# pilot.net
KiCad netlist of a schematic drawn in EAGLE
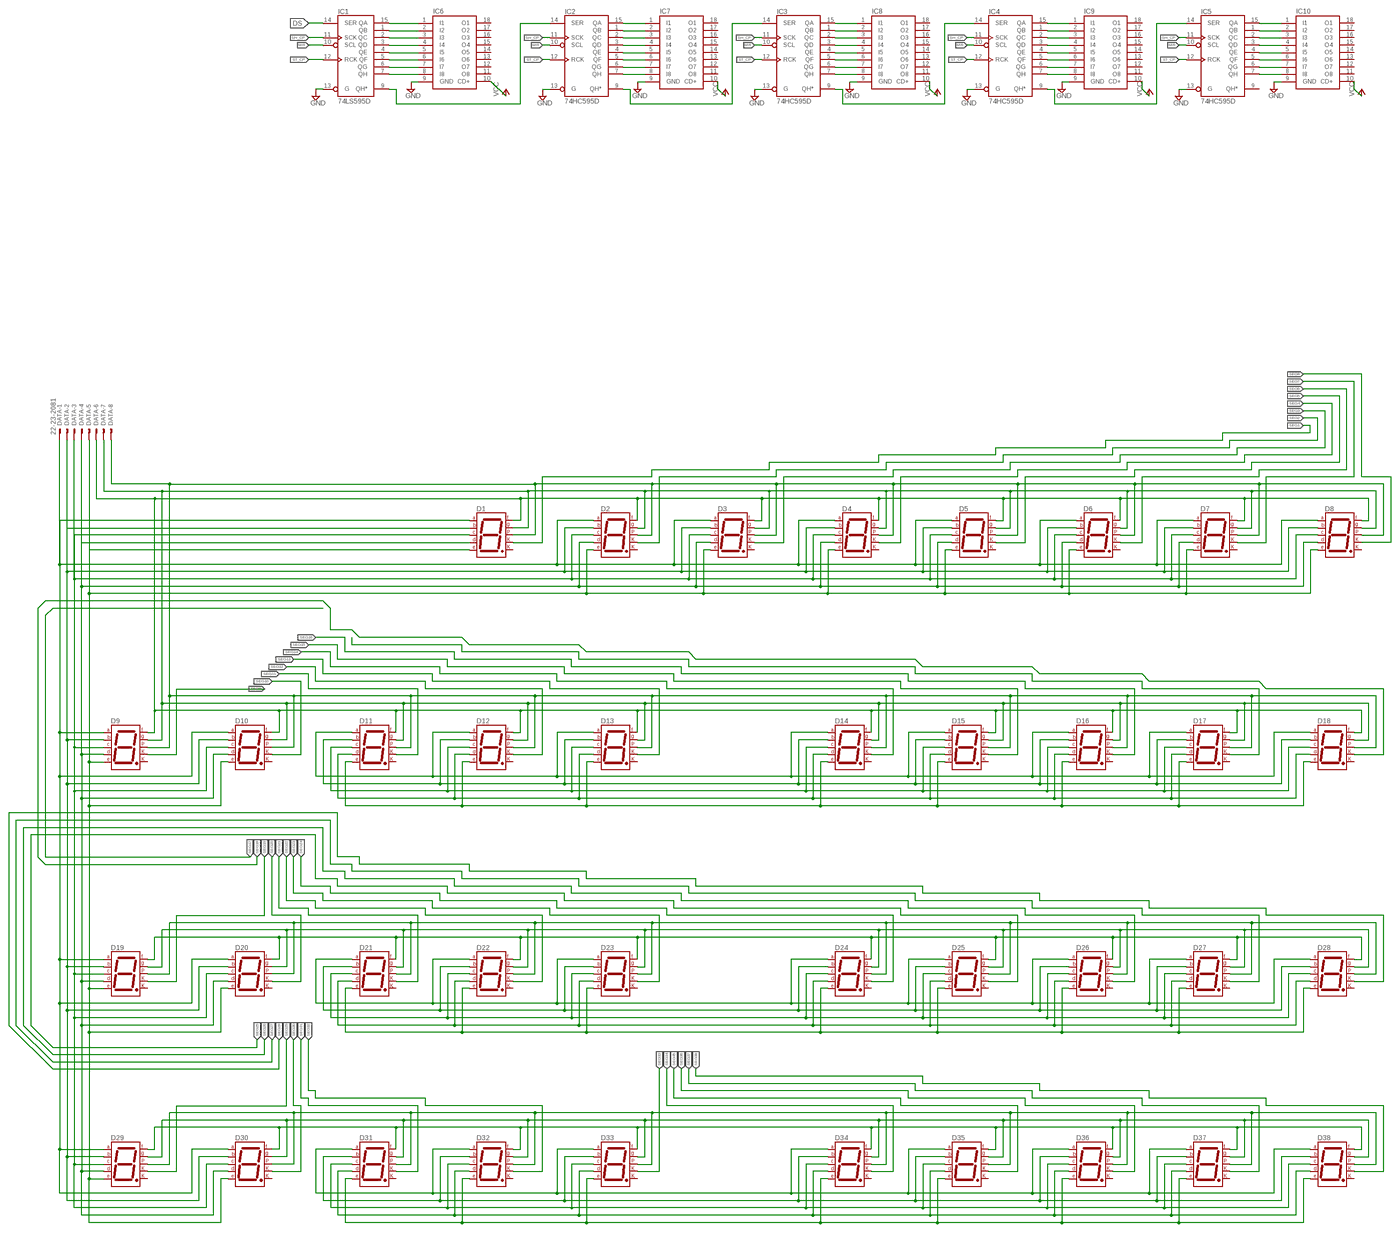
[diagram p0: schematic, sheet 1, overview]
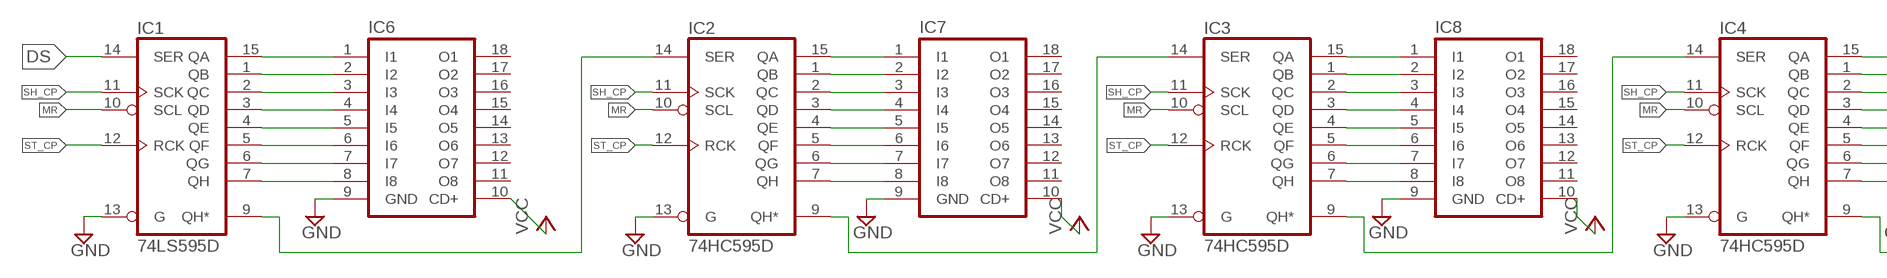
[diagram p1: schematic, sheet 1, part 1 of 4]
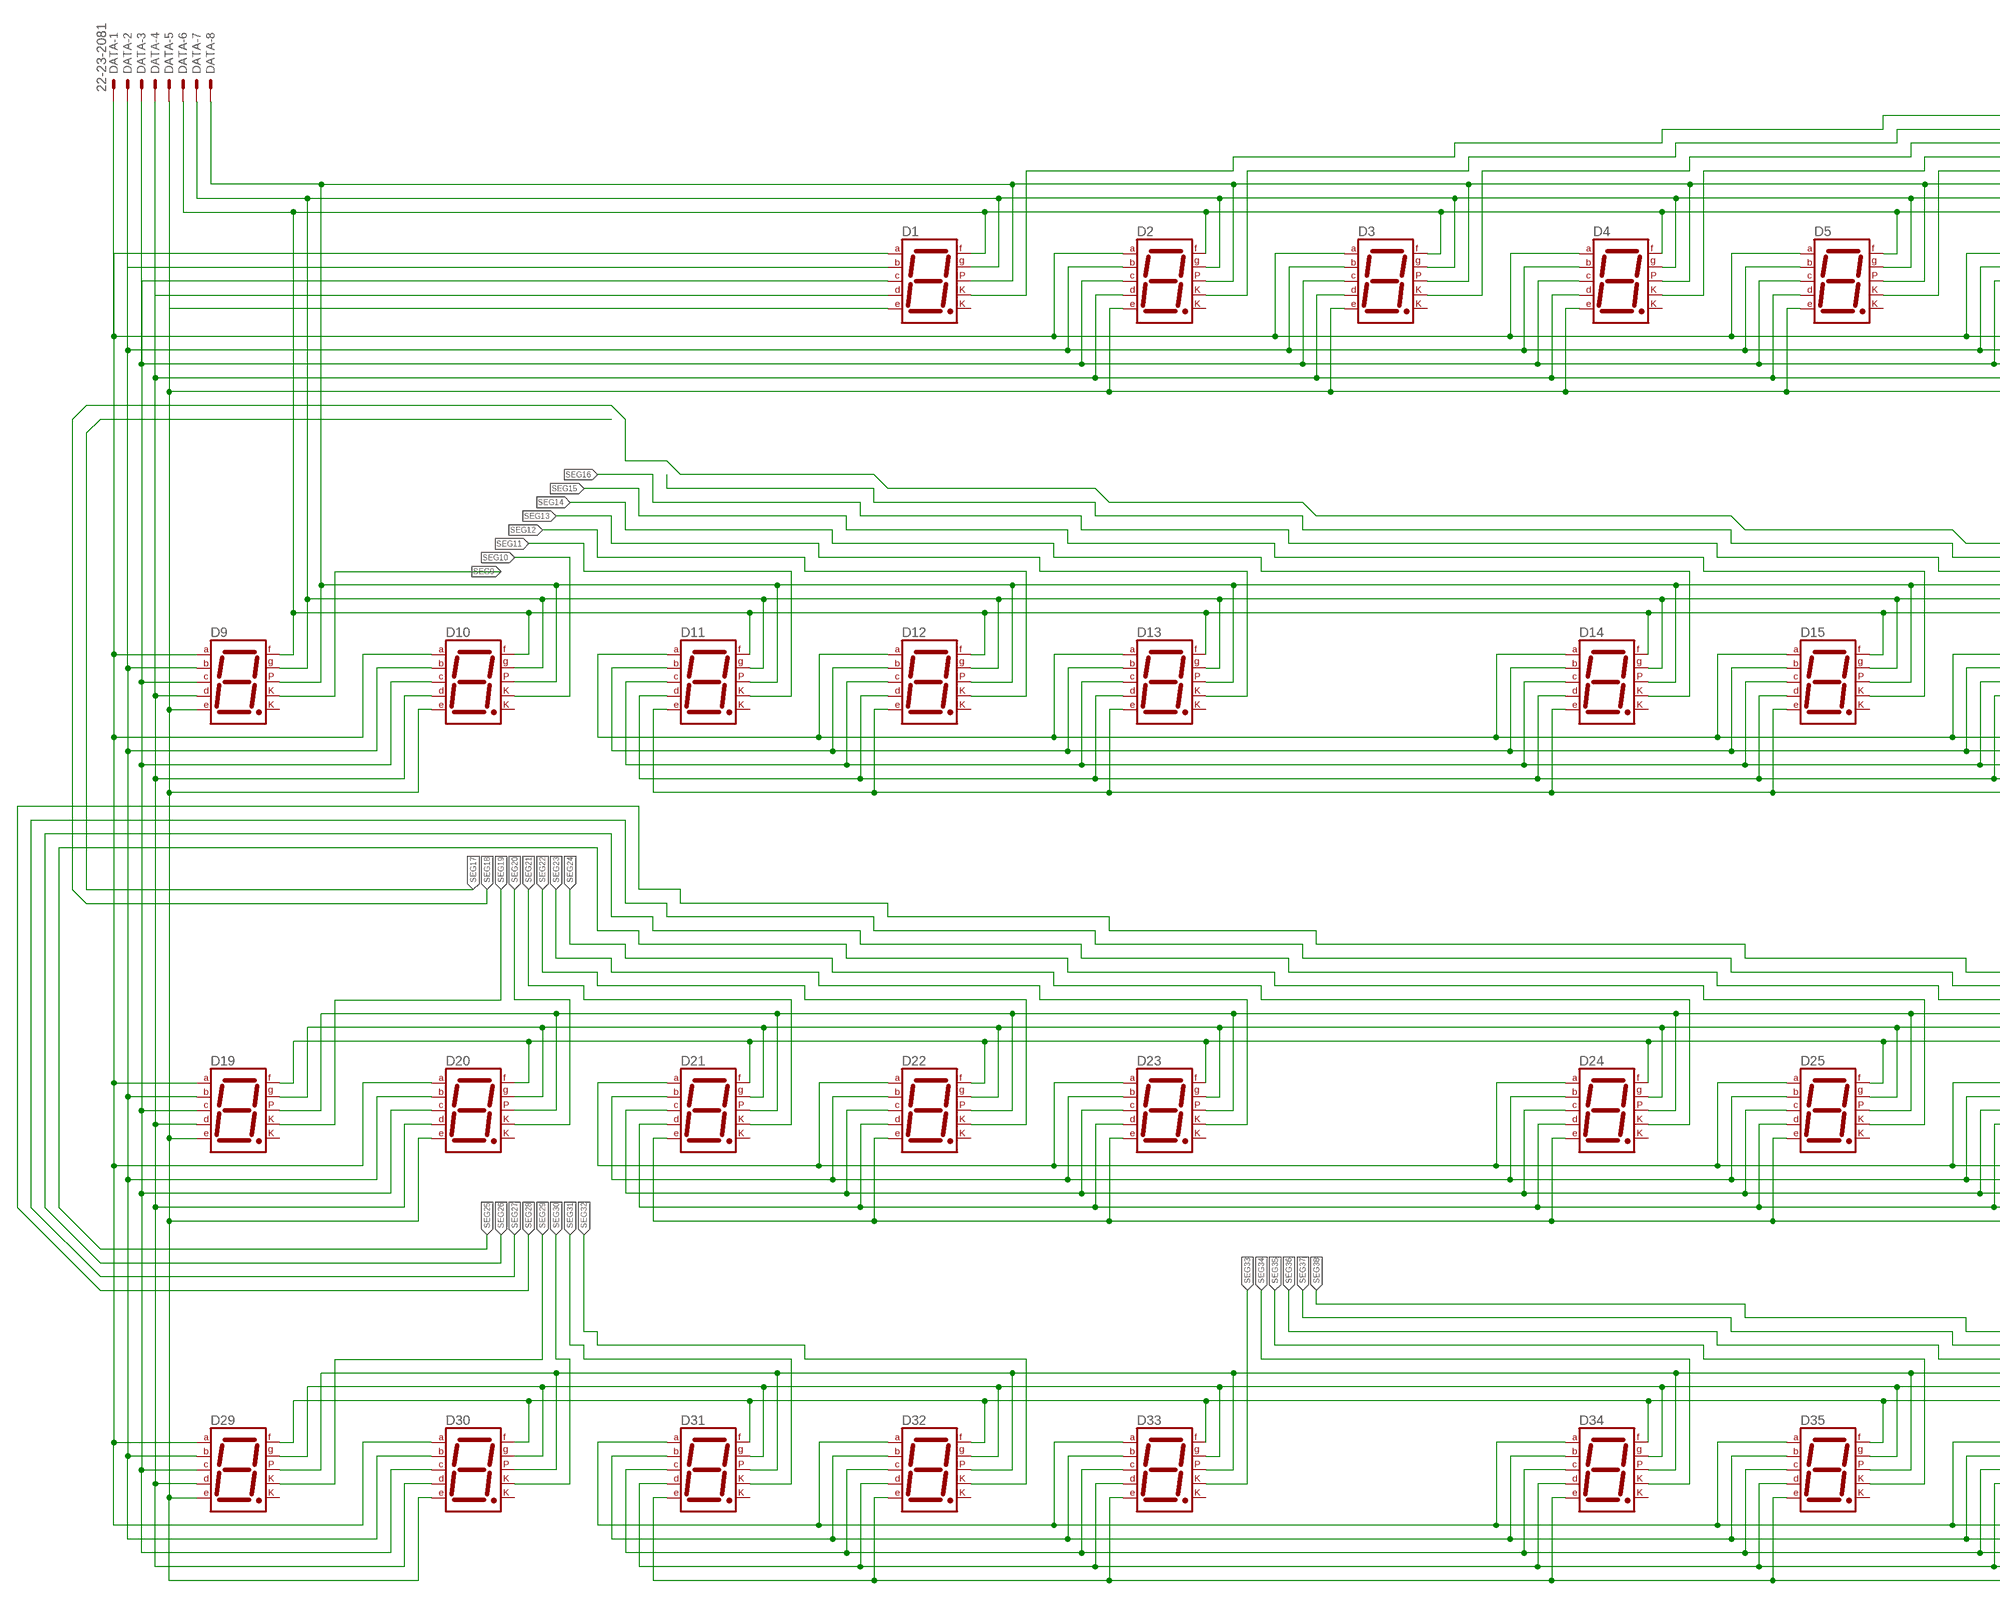
[diagram p2: schematic, sheet 1, part 2 of 4]
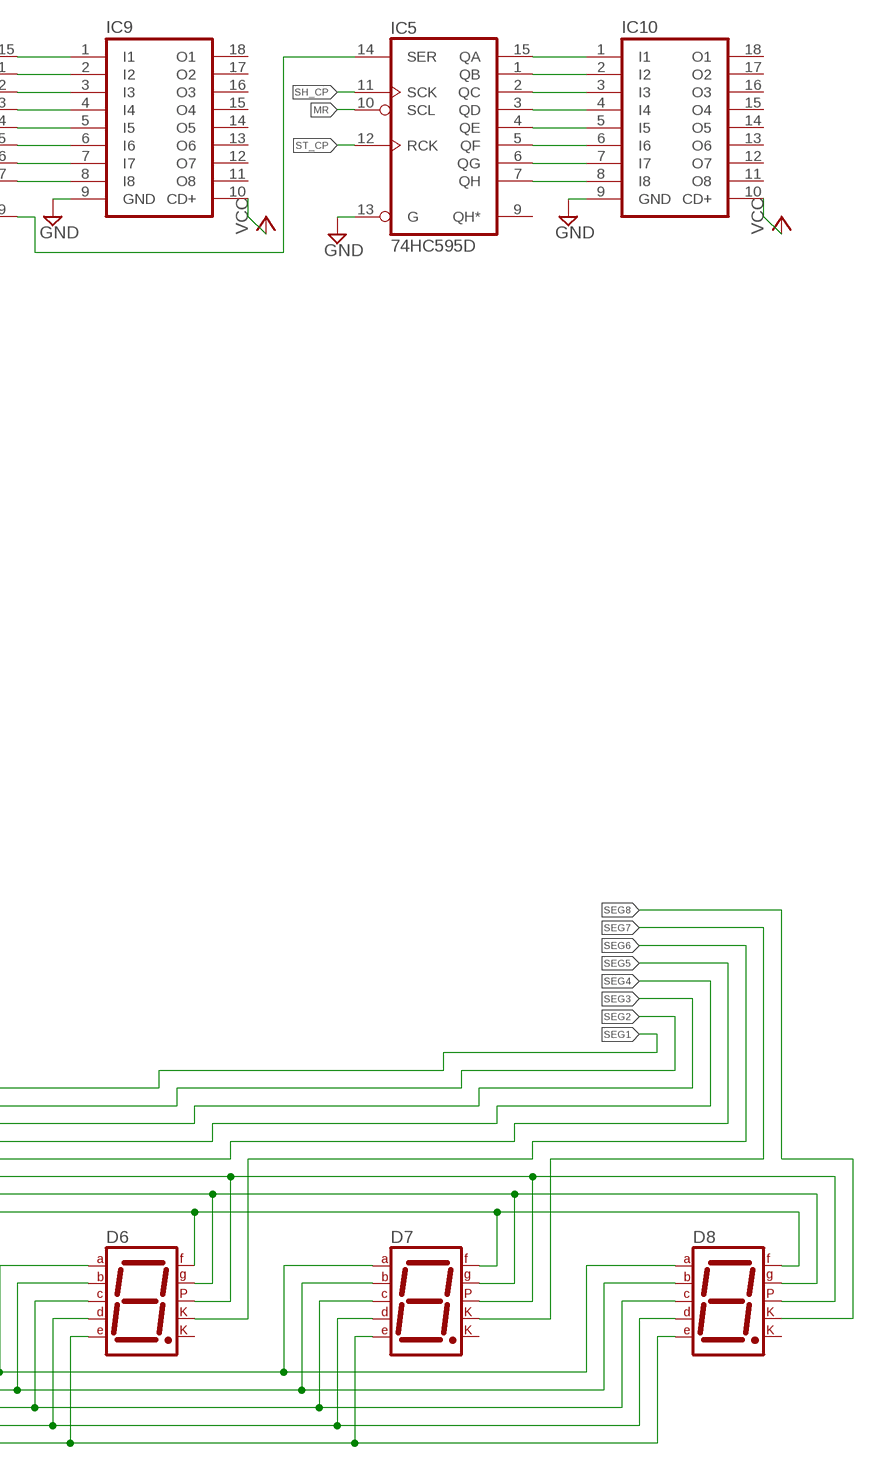
[diagram p3: schematic, sheet 1, part 3 of 4]
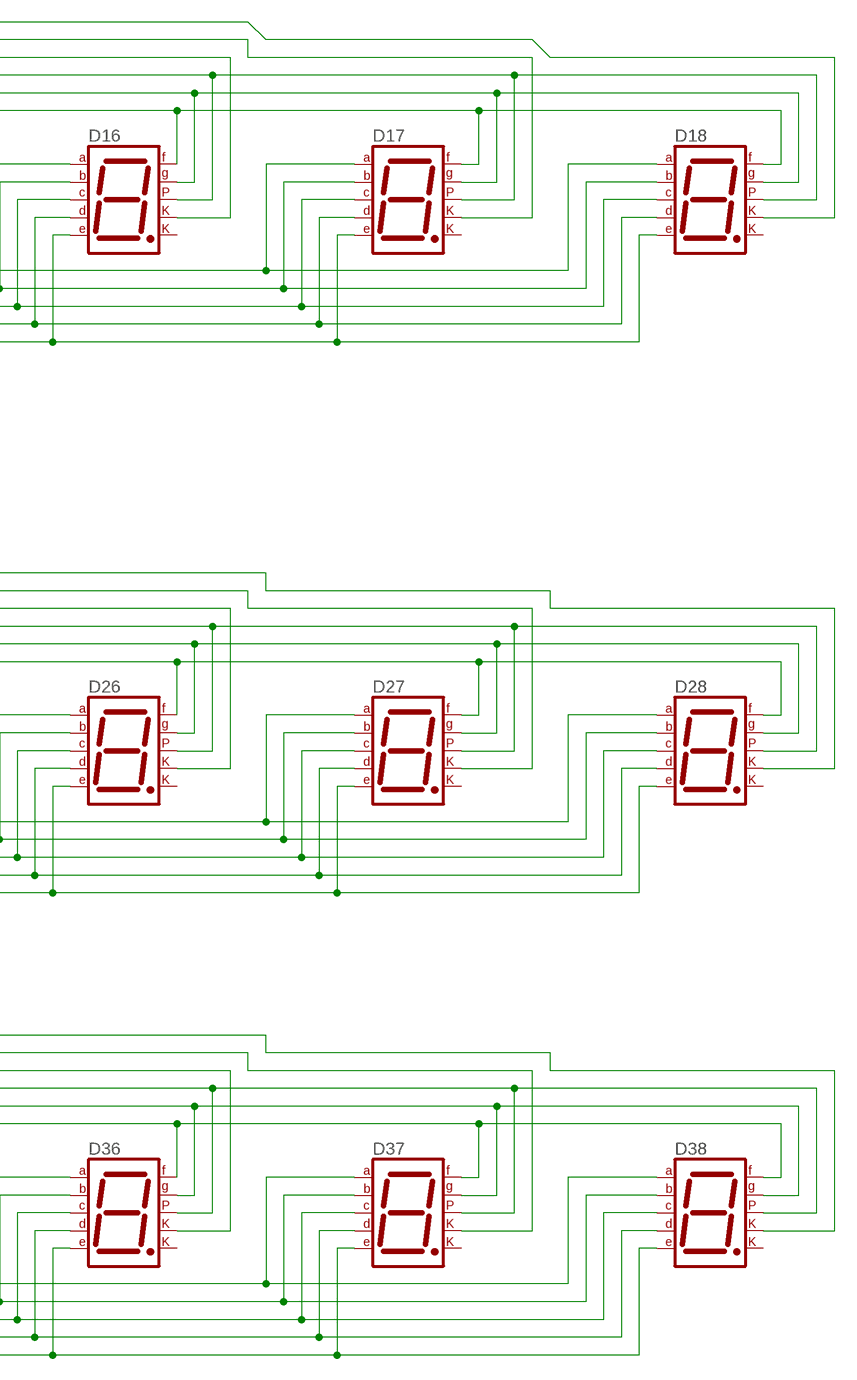
[diagram p4: schematic, sheet 1, part 4 of 4]

(export (version "E")
  (design (tool "Eeschema 10.0.6"))
  (components
    (comp (ref "D1")
      (value "7SEG-CK")
      (footprint "eagle-import:7SEG-13")
      (libsource (lib "eagle-import") (part "7SEG-CK"))
    )
    (comp (ref "D2")
      (value "7SEG-CK")
      (footprint "eagle-import:7SEG-13")
      (libsource (lib "eagle-import") (part "7SEG-CK"))
    )
    (comp (ref "D3")
      (value "7SEG-CK")
      (footprint "eagle-import:7SEG-13")
      (libsource (lib "eagle-import") (part "7SEG-CK"))
    )
    (comp (ref "D4")
      (value "7SEG-CK")
      (footprint "eagle-import:7SEG-13")
      (libsource (lib "eagle-import") (part "7SEG-CK"))
    )
    (comp (ref "D5")
      (value "7SEG-CK")
      (footprint "eagle-import:7SEG-13")
      (libsource (lib "eagle-import") (part "7SEG-CK"))
    )
    (comp (ref "D6")
      (value "7SEG-CK")
      (footprint "eagle-import:7SEG-13")
      (libsource (lib "eagle-import") (part "7SEG-CK"))
    )
    (comp (ref "D7")
      (value "7SEG-CK")
      (footprint "eagle-import:7SEG-13")
      (libsource (lib "eagle-import") (part "7SEG-CK"))
    )
    (comp (ref "D8")
      (value "7SEG-CK")
      (footprint "eagle-import:7SEG-13")
      (libsource (lib "eagle-import") (part "7SEG-CK"))
    )
    (comp (ref "D9")
      (value "7SEG-CK")
      (footprint "eagle-import:7SEG-13")
      (libsource (lib "eagle-import") (part "7SEG-CK"))
    )
    (comp (ref "D10")
      (value "7SEG-CK")
      (footprint "eagle-import:7SEG-13")
      (libsource (lib "eagle-import") (part "7SEG-CK"))
    )
    (comp (ref "D11")
      (value "7SEG-CK")
      (footprint "eagle-import:7SEG-13")
      (libsource (lib "eagle-import") (part "7SEG-CK"))
    )
    (comp (ref "D12")
      (value "7SEG-CK")
      (footprint "eagle-import:7SEG-13")
      (libsource (lib "eagle-import") (part "7SEG-CK"))
    )
    (comp (ref "D13")
      (value "7SEG-CK")
      (footprint "eagle-import:7SEG-13")
      (libsource (lib "eagle-import") (part "7SEG-CK"))
    )
    (comp (ref "D14")
      (value "7SEG-CK")
      (footprint "eagle-import:7SEG-13")
      (libsource (lib "eagle-import") (part "7SEG-CK"))
    )
    (comp (ref "D15")
      (value "7SEG-CK")
      (footprint "eagle-import:7SEG-13")
      (libsource (lib "eagle-import") (part "7SEG-CK"))
    )
    (comp (ref "D16")
      (value "7SEG-CK")
      (footprint "eagle-import:7SEG-13")
      (libsource (lib "eagle-import") (part "7SEG-CK"))
    )
    (comp (ref "D17")
      (value "7SEG-CK")
      (footprint "eagle-import:7SEG-13")
      (libsource (lib "eagle-import") (part "7SEG-CK"))
    )
    (comp (ref "D18")
      (value "7SEG-CK")
      (footprint "eagle-import:7SEG-13")
      (libsource (lib "eagle-import") (part "7SEG-CK"))
    )
    (comp (ref "D19")
      (value "7SEG-CK")
      (footprint "eagle-import:7SEG-13")
      (libsource (lib "eagle-import") (part "7SEG-CK"))
    )
    (comp (ref "D20")
      (value "7SEG-CK")
      (footprint "eagle-import:7SEG-13")
      (libsource (lib "eagle-import") (part "7SEG-CK"))
    )
    (comp (ref "D21")
      (value "7SEG-CK")
      (footprint "eagle-import:7SEG-13")
      (libsource (lib "eagle-import") (part "7SEG-CK"))
    )
    (comp (ref "D22")
      (value "7SEG-CK")
      (footprint "eagle-import:7SEG-13")
      (libsource (lib "eagle-import") (part "7SEG-CK"))
    )
    (comp (ref "D23")
      (value "7SEG-CK")
      (footprint "eagle-import:7SEG-13")
      (libsource (lib "eagle-import") (part "7SEG-CK"))
    )
    (comp (ref "D24")
      (value "7SEG-CK")
      (footprint "eagle-import:7SEG-13")
      (libsource (lib "eagle-import") (part "7SEG-CK"))
    )
    (comp (ref "D25")
      (value "7SEG-CK")
      (footprint "eagle-import:7SEG-13")
      (libsource (lib "eagle-import") (part "7SEG-CK"))
    )
    (comp (ref "D26")
      (value "7SEG-CK")
      (footprint "eagle-import:7SEG-13")
      (libsource (lib "eagle-import") (part "7SEG-CK"))
    )
    (comp (ref "D27")
      (value "7SEG-CK")
      (footprint "eagle-import:7SEG-13")
      (libsource (lib "eagle-import") (part "7SEG-CK"))
    )
    (comp (ref "D28")
      (value "7SEG-CK")
      (footprint "eagle-import:7SEG-13")
      (libsource (lib "eagle-import") (part "7SEG-CK"))
    )
    (comp (ref "D29")
      (value "7SEG-CK")
      (footprint "eagle-import:7SEG-13")
      (libsource (lib "eagle-import") (part "7SEG-CK"))
    )
    (comp (ref "D30")
      (value "7SEG-CK")
      (footprint "eagle-import:7SEG-13")
      (libsource (lib "eagle-import") (part "7SEG-CK"))
    )
    (comp (ref "D31")
      (value "7SEG-CK")
      (footprint "eagle-import:7SEG-13")
      (libsource (lib "eagle-import") (part "7SEG-CK"))
    )
    (comp (ref "D32")
      (value "7SEG-CK")
      (footprint "eagle-import:7SEG-13")
      (libsource (lib "eagle-import") (part "7SEG-CK"))
    )
    (comp (ref "D33")
      (value "7SEG-CK")
      (footprint "eagle-import:7SEG-13")
      (libsource (lib "eagle-import") (part "7SEG-CK"))
    )
    (comp (ref "D34")
      (value "7SEG-CK")
      (footprint "eagle-import:7SEG-13")
      (libsource (lib "eagle-import") (part "7SEG-CK"))
    )
    (comp (ref "D35")
      (value "7SEG-CK")
      (footprint "eagle-import:7SEG-13")
      (libsource (lib "eagle-import") (part "7SEG-CK"))
    )
    (comp (ref "D36")
      (value "7SEG-CK")
      (footprint "eagle-import:7SEG-13")
      (libsource (lib "eagle-import") (part "7SEG-CK"))
    )
    (comp (ref "D37")
      (value "7SEG-CK")
      (footprint "eagle-import:7SEG-13")
      (libsource (lib "eagle-import") (part "7SEG-CK"))
    )
    (comp (ref "D38")
      (value "7SEG-CK")
      (footprint "eagle-import:7SEG-13")
      (libsource (lib "eagle-import") (part "7SEG-CK"))
    )
    (comp (ref "DATA")
      (value "22-23-2081")
      (footprint "eagle-import:22-23-2081")
      (fields (field (name "MF") "MOLEX"))
      (libsource (lib "eagle-import") (part "22-23-2081"))
    )
    (comp (ref "IC1")
      (value "74LS595D")
      (footprint "eagle-import:SO16")
      (libsource (lib "eagle-import") (part "74595DLS"))
    )
    (comp (ref "IC2")
      (value "74HC595D")
      (footprint "eagle-import:SO16")
      (libsource (lib "eagle-import") (part "74595DHC"))
    )
    (comp (ref "IC3")
      (value "74HC595D")
      (footprint "eagle-import:SO16")
      (libsource (lib "eagle-import") (part "74595DHC"))
    )
    (comp (ref "IC4")
      (value "74HC595D")
      (footprint "eagle-import:SO16")
      (libsource (lib "eagle-import") (part "74595DHC"))
    )
    (comp (ref "IC5")
      (value "74HC595D")
      (footprint "eagle-import:SO16")
      (libsource (lib "eagle-import") (part "74595DHC"))
    )
    (comp (ref "IC6")
      (value "ULN2803A")
      (footprint "eagle-import:DIL18")
      (libsource (lib "eagle-import") (part "ULN2803A"))
    )
    (comp (ref "IC7")
      (value "ULN2803A")
      (footprint "eagle-import:DIL18")
      (libsource (lib "eagle-import") (part "ULN2803A"))
    )
    (comp (ref "IC8")
      (value "ULN2803A")
      (footprint "eagle-import:DIL18")
      (libsource (lib "eagle-import") (part "ULN2803A"))
    )
    (comp (ref "IC9")
      (value "ULN2803A")
      (footprint "eagle-import:DIL18")
      (libsource (lib "eagle-import") (part "ULN2803A"))
    )
    (comp (ref "IC10")
      (value "ULN2803A")
      (footprint "eagle-import:DIL18")
      (libsource (lib "eagle-import") (part "ULN2803A"))
    )
  )
  (nets
    (net (code "1") (name "DS") (class "Default")
      (node (ref "IC1") (pin "14") (pinfunction "SER_14") (pintype "input"))
    )
    (net (code "2") (name "GND") (class "Default")
      (node (ref "IC1") (pin "13") (pinfunction "G_13") (pintype "input"))
      (node (ref "IC10") (pin "9") (pinfunction "GND_9") (pintype "power_in"))
      (node (ref "IC2") (pin "13") (pinfunction "G_13") (pintype "input"))
      (node (ref "IC3") (pin "13") (pinfunction "G_13") (pintype "input"))
      (node (ref "IC4") (pin "13") (pinfunction "G_13") (pintype "input"))
      (node (ref "IC5") (pin "13") (pinfunction "G_13") (pintype "input"))
      (node (ref "IC6") (pin "9") (pinfunction "GND_9") (pintype "power_in"))
      (node (ref "IC7") (pin "9") (pinfunction "GND_9") (pintype "power_in"))
      (node (ref "IC8") (pin "9") (pinfunction "GND_9") (pintype "power_in"))
      (node (ref "IC9") (pin "9") (pinfunction "GND_9") (pintype "power_in"))
    )
    (net (code "3") (name "MR") (class "Default")
      (node (ref "IC1") (pin "10") (pinfunction "SCL_10") (pintype "input"))
      (node (ref "IC2") (pin "10") (pinfunction "SCL_10") (pintype "input"))
      (node (ref "IC3") (pin "10") (pinfunction "SCL_10") (pintype "input"))
      (node (ref "IC4") (pin "10") (pinfunction "SCL_10") (pintype "input"))
      (node (ref "IC5") (pin "10") (pinfunction "SCL_10") (pintype "input"))
    )
    (net (code "4") (name "Net-(D1-A)") (class "Default")
      (node (ref "D1") (pin "7") (pinfunction "A_7") (pintype "passive"))
      (node (ref "D10") (pin "7") (pinfunction "A_7") (pintype "passive"))
      (node (ref "D19") (pin "7") (pinfunction "A_7") (pintype "passive"))
      (node (ref "D2") (pin "7") (pinfunction "A_7") (pintype "passive"))
      (node (ref "D20") (pin "7") (pinfunction "A_7") (pintype "passive"))
      (node (ref "D29") (pin "7") (pinfunction "A_7") (pintype "passive"))
      (node (ref "D3") (pin "7") (pinfunction "A_7") (pintype "passive"))
      (node (ref "D30") (pin "7") (pinfunction "A_7") (pintype "passive"))
      (node (ref "D4") (pin "7") (pinfunction "A_7") (pintype "passive"))
      (node (ref "D5") (pin "7") (pinfunction "A_7") (pintype "passive"))
      (node (ref "D6") (pin "7") (pinfunction "A_7") (pintype "passive"))
      (node (ref "D7") (pin "7") (pinfunction "A_7") (pintype "passive"))
      (node (ref "D8") (pin "7") (pinfunction "A_7") (pintype "passive"))
      (node (ref "D9") (pin "7") (pinfunction "A_7") (pintype "passive"))
      (node (ref "DATA") (pin "1") (pinfunction "S_1") (pintype "passive"))
    )
    (net (code "5") (name "Net-(D1-B)") (class "Default")
      (node (ref "D1") (pin "6") (pinfunction "B_6") (pintype "passive"))
      (node (ref "D10") (pin "6") (pinfunction "B_6") (pintype "passive"))
      (node (ref "D19") (pin "6") (pinfunction "B_6") (pintype "passive"))
      (node (ref "D2") (pin "6") (pinfunction "B_6") (pintype "passive"))
      (node (ref "D20") (pin "6") (pinfunction "B_6") (pintype "passive"))
      (node (ref "D29") (pin "6") (pinfunction "B_6") (pintype "passive"))
      (node (ref "D3") (pin "6") (pinfunction "B_6") (pintype "passive"))
      (node (ref "D30") (pin "6") (pinfunction "B_6") (pintype "passive"))
      (node (ref "D4") (pin "6") (pinfunction "B_6") (pintype "passive"))
      (node (ref "D5") (pin "6") (pinfunction "B_6") (pintype "passive"))
      (node (ref "D6") (pin "6") (pinfunction "B_6") (pintype "passive"))
      (node (ref "D7") (pin "6") (pinfunction "B_6") (pintype "passive"))
      (node (ref "D8") (pin "6") (pinfunction "B_6") (pintype "passive"))
      (node (ref "D9") (pin "6") (pinfunction "B_6") (pintype "passive"))
      (node (ref "DATA") (pin "2") (pinfunction "S_2") (pintype "passive"))
    )
    (net (code "6") (name "Net-(D1-C)") (class "Default")
      (node (ref "D1") (pin "4") (pinfunction "C_4") (pintype "passive"))
      (node (ref "D10") (pin "4") (pinfunction "C_4") (pintype "passive"))
      (node (ref "D19") (pin "4") (pinfunction "C_4") (pintype "passive"))
      (node (ref "D2") (pin "4") (pinfunction "C_4") (pintype "passive"))
      (node (ref "D20") (pin "4") (pinfunction "C_4") (pintype "passive"))
      (node (ref "D29") (pin "4") (pinfunction "C_4") (pintype "passive"))
      (node (ref "D3") (pin "4") (pinfunction "C_4") (pintype "passive"))
      (node (ref "D30") (pin "4") (pinfunction "C_4") (pintype "passive"))
      (node (ref "D4") (pin "4") (pinfunction "C_4") (pintype "passive"))
      (node (ref "D5") (pin "4") (pinfunction "C_4") (pintype "passive"))
      (node (ref "D6") (pin "4") (pinfunction "C_4") (pintype "passive"))
      (node (ref "D7") (pin "4") (pinfunction "C_4") (pintype "passive"))
      (node (ref "D8") (pin "4") (pinfunction "C_4") (pintype "passive"))
      (node (ref "D9") (pin "4") (pinfunction "C_4") (pintype "passive"))
      (node (ref "DATA") (pin "3") (pinfunction "S_3") (pintype "passive"))
    )
    (net (code "7") (name "Net-(D1-D)") (class "Default")
      (node (ref "D1") (pin "2") (pinfunction "D_2") (pintype "passive"))
      (node (ref "D10") (pin "2") (pinfunction "D_2") (pintype "passive"))
      (node (ref "D19") (pin "2") (pinfunction "D_2") (pintype "passive"))
      (node (ref "D2") (pin "2") (pinfunction "D_2") (pintype "passive"))
      (node (ref "D20") (pin "2") (pinfunction "D_2") (pintype "passive"))
      (node (ref "D29") (pin "2") (pinfunction "D_2") (pintype "passive"))
      (node (ref "D3") (pin "2") (pinfunction "D_2") (pintype "passive"))
      (node (ref "D30") (pin "2") (pinfunction "D_2") (pintype "passive"))
      (node (ref "D4") (pin "2") (pinfunction "D_2") (pintype "passive"))
      (node (ref "D5") (pin "2") (pinfunction "D_2") (pintype "passive"))
      (node (ref "D6") (pin "2") (pinfunction "D_2") (pintype "passive"))
      (node (ref "D7") (pin "2") (pinfunction "D_2") (pintype "passive"))
      (node (ref "D8") (pin "2") (pinfunction "D_2") (pintype "passive"))
      (node (ref "D9") (pin "2") (pinfunction "D_2") (pintype "passive"))
      (node (ref "DATA") (pin "4") (pinfunction "S_4") (pintype "passive"))
    )
    (net (code "8") (name "Net-(D1-DP)") (class "Default")
      (node (ref "D1") (pin "5") (pinfunction "DP_5") (pintype "passive"))
      (node (ref "D10") (pin "5") (pinfunction "DP_5") (pintype "passive"))
      (node (ref "D11") (pin "5") (pinfunction "DP_5") (pintype "passive"))
      (node (ref "D12") (pin "5") (pinfunction "DP_5") (pintype "passive"))
      (node (ref "D13") (pin "5") (pinfunction "DP_5") (pintype "passive"))
      (node (ref "D14") (pin "5") (pinfunction "DP_5") (pintype "passive"))
      (node (ref "D15") (pin "5") (pinfunction "DP_5") (pintype "passive"))
      (node (ref "D16") (pin "5") (pinfunction "DP_5") (pintype "passive"))
      (node (ref "D17") (pin "5") (pinfunction "DP_5") (pintype "passive"))
      (node (ref "D18") (pin "5") (pinfunction "DP_5") (pintype "passive"))
      (node (ref "D2") (pin "5") (pinfunction "DP_5") (pintype "passive"))
      (node (ref "D3") (pin "5") (pinfunction "DP_5") (pintype "passive"))
      (node (ref "D4") (pin "5") (pinfunction "DP_5") (pintype "passive"))
      (node (ref "D5") (pin "5") (pinfunction "DP_5") (pintype "passive"))
      (node (ref "D6") (pin "5") (pinfunction "DP_5") (pintype "passive"))
      (node (ref "D7") (pin "5") (pinfunction "DP_5") (pintype "passive"))
      (node (ref "D8") (pin "5") (pinfunction "DP_5") (pintype "passive"))
      (node (ref "D9") (pin "5") (pinfunction "DP_5") (pintype "passive"))
      (node (ref "DATA") (pin "8") (pinfunction "S_8") (pintype "passive"))
    )
    (net (code "9") (name "Net-(D1-E)") (class "Default")
      (node (ref "D1") (pin "1") (pinfunction "E_1") (pintype "passive"))
      (node (ref "D10") (pin "1") (pinfunction "E_1") (pintype "passive"))
      (node (ref "D19") (pin "1") (pinfunction "E_1") (pintype "passive"))
      (node (ref "D2") (pin "1") (pinfunction "E_1") (pintype "passive"))
      (node (ref "D20") (pin "1") (pinfunction "E_1") (pintype "passive"))
      (node (ref "D29") (pin "1") (pinfunction "E_1") (pintype "passive"))
      (node (ref "D3") (pin "1") (pinfunction "E_1") (pintype "passive"))
      (node (ref "D30") (pin "1") (pinfunction "E_1") (pintype "passive"))
      (node (ref "D4") (pin "1") (pinfunction "E_1") (pintype "passive"))
      (node (ref "D5") (pin "1") (pinfunction "E_1") (pintype "passive"))
      (node (ref "D6") (pin "1") (pinfunction "E_1") (pintype "passive"))
      (node (ref "D7") (pin "1") (pinfunction "E_1") (pintype "passive"))
      (node (ref "D8") (pin "1") (pinfunction "E_1") (pintype "passive"))
      (node (ref "D9") (pin "1") (pinfunction "E_1") (pintype "passive"))
      (node (ref "DATA") (pin "5") (pinfunction "S_5") (pintype "passive"))
    )
    (net (code "10") (name "Net-(D1-F)") (class "Default")
      (node (ref "D1") (pin "9") (pinfunction "F_9") (pintype "passive"))
      (node (ref "D10") (pin "9") (pinfunction "F_9") (pintype "passive"))
      (node (ref "D11") (pin "9") (pinfunction "F_9") (pintype "passive"))
      (node (ref "D12") (pin "9") (pinfunction "F_9") (pintype "passive"))
      (node (ref "D13") (pin "9") (pinfunction "F_9") (pintype "passive"))
      (node (ref "D14") (pin "9") (pinfunction "F_9") (pintype "passive"))
      (node (ref "D15") (pin "9") (pinfunction "F_9") (pintype "passive"))
      (node (ref "D16") (pin "9") (pinfunction "F_9") (pintype "passive"))
      (node (ref "D17") (pin "9") (pinfunction "F_9") (pintype "passive"))
      (node (ref "D18") (pin "9") (pinfunction "F_9") (pintype "passive"))
      (node (ref "D2") (pin "9") (pinfunction "F_9") (pintype "passive"))
      (node (ref "D3") (pin "9") (pinfunction "F_9") (pintype "passive"))
      (node (ref "D4") (pin "9") (pinfunction "F_9") (pintype "passive"))
      (node (ref "D5") (pin "9") (pinfunction "F_9") (pintype "passive"))
      (node (ref "D6") (pin "9") (pinfunction "F_9") (pintype "passive"))
      (node (ref "D7") (pin "9") (pinfunction "F_9") (pintype "passive"))
      (node (ref "D8") (pin "9") (pinfunction "F_9") (pintype "passive"))
      (node (ref "D9") (pin "9") (pinfunction "F_9") (pintype "passive"))
      (node (ref "DATA") (pin "6") (pinfunction "S_6") (pintype "passive"))
    )
    (net (code "11") (name "Net-(D1-G)") (class "Default")
      (node (ref "D1") (pin "10") (pinfunction "G_10") (pintype "passive"))
      (node (ref "D10") (pin "10") (pinfunction "G_10") (pintype "passive"))
      (node (ref "D11") (pin "10") (pinfunction "G_10") (pintype "passive"))
      (node (ref "D12") (pin "10") (pinfunction "G_10") (pintype "passive"))
      (node (ref "D13") (pin "10") (pinfunction "G_10") (pintype "passive"))
      (node (ref "D2") (pin "10") (pinfunction "G_10") (pintype "passive"))
      (node (ref "D3") (pin "10") (pinfunction "G_10") (pintype "passive"))
      (node (ref "D4") (pin "10") (pinfunction "G_10") (pintype "passive"))
      (node (ref "D5") (pin "10") (pinfunction "G_10") (pintype "passive"))
      (node (ref "D6") (pin "10") (pinfunction "G_10") (pintype "passive"))
      (node (ref "D7") (pin "10") (pinfunction "G_10") (pintype "passive"))
      (node (ref "D8") (pin "10") (pinfunction "G_10") (pintype "passive"))
      (node (ref "D9") (pin "10") (pinfunction "G_10") (pintype "passive"))
      (node (ref "DATA") (pin "7") (pinfunction "S_7") (pintype "passive"))
    )
    (net (code "12") (name "Net-(D11-A)") (class "Default")
      (node (ref "D11") (pin "7") (pinfunction "A_7") (pintype "passive"))
      (node (ref "D12") (pin "7") (pinfunction "A_7") (pintype "passive"))
      (node (ref "D13") (pin "7") (pinfunction "A_7") (pintype "passive"))
    )
    (net (code "13") (name "Net-(D11-B)") (class "Default")
      (node (ref "D11") (pin "6") (pinfunction "B_6") (pintype "passive"))
      (node (ref "D12") (pin "6") (pinfunction "B_6") (pintype "passive"))
      (node (ref "D13") (pin "6") (pinfunction "B_6") (pintype "passive"))
    )
    (net (code "14") (name "Net-(D11-C)") (class "Default")
      (node (ref "D11") (pin "4") (pinfunction "C_4") (pintype "passive"))
      (node (ref "D12") (pin "4") (pinfunction "C_4") (pintype "passive"))
      (node (ref "D13") (pin "4") (pinfunction "C_4") (pintype "passive"))
    )
    (net (code "15") (name "Net-(D11-D)") (class "Default")
      (node (ref "D11") (pin "2") (pinfunction "D_2") (pintype "passive"))
      (node (ref "D12") (pin "2") (pinfunction "D_2") (pintype "passive"))
      (node (ref "D13") (pin "2") (pinfunction "D_2") (pintype "passive"))
    )
    (net (code "16") (name "Net-(D11-E)") (class "Default")
      (node (ref "D11") (pin "1") (pinfunction "E_1") (pintype "passive"))
      (node (ref "D12") (pin "1") (pinfunction "E_1") (pintype "passive"))
      (node (ref "D13") (pin "1") (pinfunction "E_1") (pintype "passive"))
    )
    (net (code "17") (name "Net-(D14-A)") (class "Default")
      (node (ref "D14") (pin "7") (pinfunction "A_7") (pintype "passive"))
      (node (ref "D15") (pin "7") (pinfunction "A_7") (pintype "passive"))
      (node (ref "D16") (pin "7") (pinfunction "A_7") (pintype "passive"))
      (node (ref "D17") (pin "7") (pinfunction "A_7") (pintype "passive"))
      (node (ref "D18") (pin "7") (pinfunction "A_7") (pintype "passive"))
    )
    (net (code "18") (name "Net-(D14-B)") (class "Default")
      (node (ref "D14") (pin "6") (pinfunction "B_6") (pintype "passive"))
      (node (ref "D15") (pin "6") (pinfunction "B_6") (pintype "passive"))
      (node (ref "D16") (pin "6") (pinfunction "B_6") (pintype "passive"))
      (node (ref "D17") (pin "6") (pinfunction "B_6") (pintype "passive"))
      (node (ref "D18") (pin "6") (pinfunction "B_6") (pintype "passive"))
    )
    (net (code "19") (name "Net-(D14-C)") (class "Default")
      (node (ref "D14") (pin "4") (pinfunction "C_4") (pintype "passive"))
      (node (ref "D15") (pin "4") (pinfunction "C_4") (pintype "passive"))
      (node (ref "D16") (pin "4") (pinfunction "C_4") (pintype "passive"))
      (node (ref "D17") (pin "4") (pinfunction "C_4") (pintype "passive"))
      (node (ref "D18") (pin "4") (pinfunction "C_4") (pintype "passive"))
    )
    (net (code "20") (name "Net-(D14-D)") (class "Default")
      (node (ref "D14") (pin "2") (pinfunction "D_2") (pintype "passive"))
      (node (ref "D15") (pin "2") (pinfunction "D_2") (pintype "passive"))
      (node (ref "D16") (pin "2") (pinfunction "D_2") (pintype "passive"))
      (node (ref "D17") (pin "2") (pinfunction "D_2") (pintype "passive"))
      (node (ref "D18") (pin "2") (pinfunction "D_2") (pintype "passive"))
    )
    (net (code "21") (name "Net-(D14-E)") (class "Default")
      (node (ref "D14") (pin "1") (pinfunction "E_1") (pintype "passive"))
      (node (ref "D15") (pin "1") (pinfunction "E_1") (pintype "passive"))
      (node (ref "D16") (pin "1") (pinfunction "E_1") (pintype "passive"))
      (node (ref "D17") (pin "1") (pinfunction "E_1") (pintype "passive"))
      (node (ref "D18") (pin "1") (pinfunction "E_1") (pintype "passive"))
    )
    (net (code "22") (name "Net-(D14-G)") (class "Default")
      (node (ref "D14") (pin "10") (pinfunction "G_10") (pintype "passive"))
      (node (ref "D15") (pin "10") (pinfunction "G_10") (pintype "passive"))
      (node (ref "D16") (pin "10") (pinfunction "G_10") (pintype "passive"))
      (node (ref "D17") (pin "10") (pinfunction "G_10") (pintype "passive"))
      (node (ref "D18") (pin "10") (pinfunction "G_10") (pintype "passive"))
    )
    (net (code "23") (name "Net-(D19-DP)") (class "Default")
      (node (ref "D19") (pin "5") (pinfunction "DP_5") (pintype "passive"))
      (node (ref "D20") (pin "5") (pinfunction "DP_5") (pintype "passive"))
      (node (ref "D21") (pin "5") (pinfunction "DP_5") (pintype "passive"))
      (node (ref "D22") (pin "5") (pinfunction "DP_5") (pintype "passive"))
      (node (ref "D23") (pin "5") (pinfunction "DP_5") (pintype "passive"))
      (node (ref "D24") (pin "5") (pinfunction "DP_5") (pintype "passive"))
      (node (ref "D25") (pin "5") (pinfunction "DP_5") (pintype "passive"))
      (node (ref "D26") (pin "5") (pinfunction "DP_5") (pintype "passive"))
      (node (ref "D27") (pin "5") (pinfunction "DP_5") (pintype "passive"))
      (node (ref "D28") (pin "5") (pinfunction "DP_5") (pintype "passive"))
    )
    (net (code "24") (name "Net-(D19-F)") (class "Default")
      (node (ref "D19") (pin "9") (pinfunction "F_9") (pintype "passive"))
      (node (ref "D20") (pin "9") (pinfunction "F_9") (pintype "passive"))
      (node (ref "D21") (pin "9") (pinfunction "F_9") (pintype "passive"))
      (node (ref "D22") (pin "9") (pinfunction "F_9") (pintype "passive"))
      (node (ref "D23") (pin "9") (pinfunction "F_9") (pintype "passive"))
      (node (ref "D24") (pin "9") (pinfunction "F_9") (pintype "passive"))
      (node (ref "D25") (pin "9") (pinfunction "F_9") (pintype "passive"))
      (node (ref "D26") (pin "9") (pinfunction "F_9") (pintype "passive"))
      (node (ref "D27") (pin "9") (pinfunction "F_9") (pintype "passive"))
      (node (ref "D28") (pin "9") (pinfunction "F_9") (pintype "passive"))
    )
    (net (code "25") (name "Net-(D19-G)") (class "Default")
      (node (ref "D19") (pin "10") (pinfunction "G_10") (pintype "passive"))
      (node (ref "D20") (pin "10") (pinfunction "G_10") (pintype "passive"))
      (node (ref "D21") (pin "10") (pinfunction "G_10") (pintype "passive"))
      (node (ref "D22") (pin "10") (pinfunction "G_10") (pintype "passive"))
      (node (ref "D23") (pin "10") (pinfunction "G_10") (pintype "passive"))
    )
    (net (code "26") (name "Net-(D21-A)") (class "Default")
      (node (ref "D21") (pin "7") (pinfunction "A_7") (pintype "passive"))
      (node (ref "D22") (pin "7") (pinfunction "A_7") (pintype "passive"))
      (node (ref "D23") (pin "7") (pinfunction "A_7") (pintype "passive"))
    )
    (net (code "27") (name "Net-(D21-B)") (class "Default")
      (node (ref "D21") (pin "6") (pinfunction "B_6") (pintype "passive"))
      (node (ref "D22") (pin "6") (pinfunction "B_6") (pintype "passive"))
      (node (ref "D23") (pin "6") (pinfunction "B_6") (pintype "passive"))
    )
    (net (code "28") (name "Net-(D21-C)") (class "Default")
      (node (ref "D21") (pin "4") (pinfunction "C_4") (pintype "passive"))
      (node (ref "D22") (pin "4") (pinfunction "C_4") (pintype "passive"))
      (node (ref "D23") (pin "4") (pinfunction "C_4") (pintype "passive"))
    )
    (net (code "29") (name "Net-(D21-D)") (class "Default")
      (node (ref "D21") (pin "2") (pinfunction "D_2") (pintype "passive"))
      (node (ref "D22") (pin "2") (pinfunction "D_2") (pintype "passive"))
      (node (ref "D23") (pin "2") (pinfunction "D_2") (pintype "passive"))
    )
    (net (code "30") (name "Net-(D21-E)") (class "Default")
      (node (ref "D21") (pin "1") (pinfunction "E_1") (pintype "passive"))
      (node (ref "D22") (pin "1") (pinfunction "E_1") (pintype "passive"))
      (node (ref "D23") (pin "1") (pinfunction "E_1") (pintype "passive"))
    )
    (net (code "31") (name "Net-(D24-A)") (class "Default")
      (node (ref "D24") (pin "7") (pinfunction "A_7") (pintype "passive"))
      (node (ref "D25") (pin "7") (pinfunction "A_7") (pintype "passive"))
      (node (ref "D26") (pin "7") (pinfunction "A_7") (pintype "passive"))
      (node (ref "D27") (pin "7") (pinfunction "A_7") (pintype "passive"))
      (node (ref "D28") (pin "7") (pinfunction "A_7") (pintype "passive"))
    )
    (net (code "32") (name "Net-(D24-B)") (class "Default")
      (node (ref "D24") (pin "6") (pinfunction "B_6") (pintype "passive"))
      (node (ref "D25") (pin "6") (pinfunction "B_6") (pintype "passive"))
      (node (ref "D26") (pin "6") (pinfunction "B_6") (pintype "passive"))
      (node (ref "D27") (pin "6") (pinfunction "B_6") (pintype "passive"))
      (node (ref "D28") (pin "6") (pinfunction "B_6") (pintype "passive"))
    )
    (net (code "33") (name "Net-(D24-C)") (class "Default")
      (node (ref "D24") (pin "4") (pinfunction "C_4") (pintype "passive"))
      (node (ref "D25") (pin "4") (pinfunction "C_4") (pintype "passive"))
      (node (ref "D26") (pin "4") (pinfunction "C_4") (pintype "passive"))
      (node (ref "D27") (pin "4") (pinfunction "C_4") (pintype "passive"))
      (node (ref "D28") (pin "4") (pinfunction "C_4") (pintype "passive"))
    )
    (net (code "34") (name "Net-(D24-D)") (class "Default")
      (node (ref "D24") (pin "2") (pinfunction "D_2") (pintype "passive"))
      (node (ref "D25") (pin "2") (pinfunction "D_2") (pintype "passive"))
      (node (ref "D26") (pin "2") (pinfunction "D_2") (pintype "passive"))
      (node (ref "D27") (pin "2") (pinfunction "D_2") (pintype "passive"))
      (node (ref "D28") (pin "2") (pinfunction "D_2") (pintype "passive"))
    )
    (net (code "35") (name "Net-(D24-E)") (class "Default")
      (node (ref "D24") (pin "1") (pinfunction "E_1") (pintype "passive"))
      (node (ref "D25") (pin "1") (pinfunction "E_1") (pintype "passive"))
      (node (ref "D26") (pin "1") (pinfunction "E_1") (pintype "passive"))
      (node (ref "D27") (pin "1") (pinfunction "E_1") (pintype "passive"))
      (node (ref "D28") (pin "1") (pinfunction "E_1") (pintype "passive"))
    )
    (net (code "36") (name "Net-(D24-G)") (class "Default")
      (node (ref "D24") (pin "10") (pinfunction "G_10") (pintype "passive"))
      (node (ref "D25") (pin "10") (pinfunction "G_10") (pintype "passive"))
      (node (ref "D26") (pin "10") (pinfunction "G_10") (pintype "passive"))
      (node (ref "D27") (pin "10") (pinfunction "G_10") (pintype "passive"))
      (node (ref "D28") (pin "10") (pinfunction "G_10") (pintype "passive"))
    )
    (net (code "37") (name "Net-(D29-DP)") (class "Default")
      (node (ref "D29") (pin "5") (pinfunction "DP_5") (pintype "passive"))
      (node (ref "D30") (pin "5") (pinfunction "DP_5") (pintype "passive"))
      (node (ref "D31") (pin "5") (pinfunction "DP_5") (pintype "passive"))
      (node (ref "D32") (pin "5") (pinfunction "DP_5") (pintype "passive"))
      (node (ref "D33") (pin "5") (pinfunction "DP_5") (pintype "passive"))
      (node (ref "D34") (pin "5") (pinfunction "DP_5") (pintype "passive"))
      (node (ref "D35") (pin "5") (pinfunction "DP_5") (pintype "passive"))
      (node (ref "D36") (pin "5") (pinfunction "DP_5") (pintype "passive"))
      (node (ref "D37") (pin "5") (pinfunction "DP_5") (pintype "passive"))
      (node (ref "D38") (pin "5") (pinfunction "DP_5") (pintype "passive"))
    )
    (net (code "38") (name "Net-(D29-F)") (class "Default")
      (node (ref "D29") (pin "9") (pinfunction "F_9") (pintype "passive"))
      (node (ref "D30") (pin "9") (pinfunction "F_9") (pintype "passive"))
      (node (ref "D31") (pin "9") (pinfunction "F_9") (pintype "passive"))
      (node (ref "D32") (pin "9") (pinfunction "F_9") (pintype "passive"))
      (node (ref "D33") (pin "9") (pinfunction "F_9") (pintype "passive"))
      (node (ref "D34") (pin "9") (pinfunction "F_9") (pintype "passive"))
      (node (ref "D35") (pin "9") (pinfunction "F_9") (pintype "passive"))
      (node (ref "D36") (pin "9") (pinfunction "F_9") (pintype "passive"))
      (node (ref "D37") (pin "9") (pinfunction "F_9") (pintype "passive"))
      (node (ref "D38") (pin "9") (pinfunction "F_9") (pintype "passive"))
    )
    (net (code "39") (name "Net-(D29-G)") (class "Default")
      (node (ref "D29") (pin "10") (pinfunction "G_10") (pintype "passive"))
      (node (ref "D30") (pin "10") (pinfunction "G_10") (pintype "passive"))
      (node (ref "D31") (pin "10") (pinfunction "G_10") (pintype "passive"))
      (node (ref "D32") (pin "10") (pinfunction "G_10") (pintype "passive"))
      (node (ref "D33") (pin "10") (pinfunction "G_10") (pintype "passive"))
    )
    (net (code "40") (name "Net-(D31-A)") (class "Default")
      (node (ref "D31") (pin "7") (pinfunction "A_7") (pintype "passive"))
      (node (ref "D32") (pin "7") (pinfunction "A_7") (pintype "passive"))
      (node (ref "D33") (pin "7") (pinfunction "A_7") (pintype "passive"))
    )
    (net (code "41") (name "Net-(D31-B)") (class "Default")
      (node (ref "D31") (pin "6") (pinfunction "B_6") (pintype "passive"))
      (node (ref "D32") (pin "6") (pinfunction "B_6") (pintype "passive"))
      (node (ref "D33") (pin "6") (pinfunction "B_6") (pintype "passive"))
    )
    (net (code "42") (name "Net-(D31-C)") (class "Default")
      (node (ref "D31") (pin "4") (pinfunction "C_4") (pintype "passive"))
      (node (ref "D32") (pin "4") (pinfunction "C_4") (pintype "passive"))
      (node (ref "D33") (pin "4") (pinfunction "C_4") (pintype "passive"))
    )
    (net (code "43") (name "Net-(D31-D)") (class "Default")
      (node (ref "D31") (pin "2") (pinfunction "D_2") (pintype "passive"))
      (node (ref "D32") (pin "2") (pinfunction "D_2") (pintype "passive"))
      (node (ref "D33") (pin "2") (pinfunction "D_2") (pintype "passive"))
    )
    (net (code "44") (name "Net-(D31-E)") (class "Default")
      (node (ref "D31") (pin "1") (pinfunction "E_1") (pintype "passive"))
      (node (ref "D32") (pin "1") (pinfunction "E_1") (pintype "passive"))
      (node (ref "D33") (pin "1") (pinfunction "E_1") (pintype "passive"))
    )
    (net (code "45") (name "Net-(D34-A)") (class "Default")
      (node (ref "D34") (pin "7") (pinfunction "A_7") (pintype "passive"))
      (node (ref "D35") (pin "7") (pinfunction "A_7") (pintype "passive"))
      (node (ref "D36") (pin "7") (pinfunction "A_7") (pintype "passive"))
      (node (ref "D37") (pin "7") (pinfunction "A_7") (pintype "passive"))
      (node (ref "D38") (pin "7") (pinfunction "A_7") (pintype "passive"))
    )
    (net (code "46") (name "Net-(D34-B)") (class "Default")
      (node (ref "D34") (pin "6") (pinfunction "B_6") (pintype "passive"))
      (node (ref "D35") (pin "6") (pinfunction "B_6") (pintype "passive"))
      (node (ref "D36") (pin "6") (pinfunction "B_6") (pintype "passive"))
      (node (ref "D37") (pin "6") (pinfunction "B_6") (pintype "passive"))
      (node (ref "D38") (pin "6") (pinfunction "B_6") (pintype "passive"))
    )
    (net (code "47") (name "Net-(D34-C)") (class "Default")
      (node (ref "D34") (pin "4") (pinfunction "C_4") (pintype "passive"))
      (node (ref "D35") (pin "4") (pinfunction "C_4") (pintype "passive"))
      (node (ref "D36") (pin "4") (pinfunction "C_4") (pintype "passive"))
      (node (ref "D37") (pin "4") (pinfunction "C_4") (pintype "passive"))
      (node (ref "D38") (pin "4") (pinfunction "C_4") (pintype "passive"))
    )
    (net (code "48") (name "Net-(D34-D)") (class "Default")
      (node (ref "D34") (pin "2") (pinfunction "D_2") (pintype "passive"))
      (node (ref "D35") (pin "2") (pinfunction "D_2") (pintype "passive"))
      (node (ref "D36") (pin "2") (pinfunction "D_2") (pintype "passive"))
      (node (ref "D37") (pin "2") (pinfunction "D_2") (pintype "passive"))
      (node (ref "D38") (pin "2") (pinfunction "D_2") (pintype "passive"))
    )
    (net (code "49") (name "Net-(D34-E)") (class "Default")
      (node (ref "D34") (pin "1") (pinfunction "E_1") (pintype "passive"))
      (node (ref "D35") (pin "1") (pinfunction "E_1") (pintype "passive"))
      (node (ref "D36") (pin "1") (pinfunction "E_1") (pintype "passive"))
      (node (ref "D37") (pin "1") (pinfunction "E_1") (pintype "passive"))
      (node (ref "D38") (pin "1") (pinfunction "E_1") (pintype "passive"))
    )
    (net (code "50") (name "Net-(D34-G)") (class "Default")
      (node (ref "D34") (pin "10") (pinfunction "G_10") (pintype "passive"))
      (node (ref "D35") (pin "10") (pinfunction "G_10") (pintype "passive"))
      (node (ref "D36") (pin "10") (pinfunction "G_10") (pintype "passive"))
      (node (ref "D37") (pin "10") (pinfunction "G_10") (pintype "passive"))
      (node (ref "D38") (pin "10") (pinfunction "G_10") (pintype "passive"))
    )
    (net (code "51") (name "Net-(IC1A-QA)") (class "Default")
      (node (ref "IC1") (pin "15") (pinfunction "QA_15") (pintype "tri_state"))
      (node (ref "IC6") (pin "1") (pinfunction "I1_1") (pintype "input"))
    )
    (net (code "52") (name "Net-(IC1A-QB)") (class "Default")
      (node (ref "IC1") (pin "1") (pinfunction "QB_1") (pintype "tri_state"))
      (node (ref "IC6") (pin "2") (pinfunction "I2_2") (pintype "input"))
    )
    (net (code "53") (name "Net-(IC1A-QC)") (class "Default")
      (node (ref "IC1") (pin "2") (pinfunction "QC_2") (pintype "tri_state"))
      (node (ref "IC6") (pin "3") (pinfunction "I3_3") (pintype "input"))
    )
    (net (code "54") (name "Net-(IC1A-QD)") (class "Default")
      (node (ref "IC1") (pin "3") (pinfunction "QD_3") (pintype "tri_state"))
      (node (ref "IC6") (pin "4") (pinfunction "I4_4") (pintype "input"))
    )
    (net (code "55") (name "Net-(IC1A-QE)") (class "Default")
      (node (ref "IC1") (pin "4") (pinfunction "QE_4") (pintype "tri_state"))
      (node (ref "IC6") (pin "5") (pinfunction "I5_5") (pintype "input"))
    )
    (net (code "56") (name "Net-(IC1A-QF)") (class "Default")
      (node (ref "IC1") (pin "5") (pinfunction "QF_5") (pintype "tri_state"))
      (node (ref "IC6") (pin "6") (pinfunction "I6_6") (pintype "input"))
    )
    (net (code "57") (name "Net-(IC1A-QG)") (class "Default")
      (node (ref "IC1") (pin "6") (pinfunction "QG_6") (pintype "tri_state"))
      (node (ref "IC6") (pin "7") (pinfunction "I7_7") (pintype "input"))
    )
    (net (code "58") (name "Net-(IC1A-QH)") (class "Default")
      (node (ref "IC1") (pin "7") (pinfunction "QH_7") (pintype "tri_state"))
      (node (ref "IC6") (pin "8") (pinfunction "I8_8") (pintype "input"))
    )
    (net (code "59") (name "Net-(IC1A-QH*)") (class "Default")
      (node (ref "IC1") (pin "9") (pinfunction "QH*_9") (pintype "tri_state"))
      (node (ref "IC2") (pin "14") (pinfunction "SER_14") (pintype "input"))
    )
    (net (code "60") (name "Net-(IC2A-QA)") (class "Default")
      (node (ref "IC2") (pin "15") (pinfunction "QA_15") (pintype "tri_state"))
      (node (ref "IC7") (pin "1") (pinfunction "I1_1") (pintype "input"))
    )
    (net (code "61") (name "Net-(IC2A-QB)") (class "Default")
      (node (ref "IC2") (pin "1") (pinfunction "QB_1") (pintype "tri_state"))
      (node (ref "IC7") (pin "2") (pinfunction "I2_2") (pintype "input"))
    )
    (net (code "62") (name "Net-(IC2A-QC)") (class "Default")
      (node (ref "IC2") (pin "2") (pinfunction "QC_2") (pintype "tri_state"))
      (node (ref "IC7") (pin "3") (pinfunction "I3_3") (pintype "input"))
    )
    (net (code "63") (name "Net-(IC2A-QD)") (class "Default")
      (node (ref "IC2") (pin "3") (pinfunction "QD_3") (pintype "tri_state"))
      (node (ref "IC7") (pin "4") (pinfunction "I4_4") (pintype "input"))
    )
    (net (code "64") (name "Net-(IC2A-QE)") (class "Default")
      (node (ref "IC2") (pin "4") (pinfunction "QE_4") (pintype "tri_state"))
      (node (ref "IC7") (pin "5") (pinfunction "I5_5") (pintype "input"))
    )
    (net (code "65") (name "Net-(IC2A-QF)") (class "Default")
      (node (ref "IC2") (pin "5") (pinfunction "QF_5") (pintype "tri_state"))
      (node (ref "IC7") (pin "6") (pinfunction "I6_6") (pintype "input"))
    )
    (net (code "66") (name "Net-(IC2A-QG)") (class "Default")
      (node (ref "IC2") (pin "6") (pinfunction "QG_6") (pintype "tri_state"))
      (node (ref "IC7") (pin "7") (pinfunction "I7_7") (pintype "input"))
    )
    (net (code "67") (name "Net-(IC2A-QH)") (class "Default")
      (node (ref "IC2") (pin "7") (pinfunction "QH_7") (pintype "tri_state"))
      (node (ref "IC7") (pin "8") (pinfunction "I8_8") (pintype "input"))
    )
    (net (code "68") (name "Net-(IC2A-QH*)") (class "Default")
      (node (ref "IC2") (pin "9") (pinfunction "QH*_9") (pintype "tri_state"))
      (node (ref "IC3") (pin "14") (pinfunction "SER_14") (pintype "input"))
    )
    (net (code "69") (name "Net-(IC3A-QA)") (class "Default")
      (node (ref "IC3") (pin "15") (pinfunction "QA_15") (pintype "tri_state"))
      (node (ref "IC8") (pin "1") (pinfunction "I1_1") (pintype "input"))
    )
    (net (code "70") (name "Net-(IC3A-QB)") (class "Default")
      (node (ref "IC3") (pin "1") (pinfunction "QB_1") (pintype "tri_state"))
      (node (ref "IC8") (pin "2") (pinfunction "I2_2") (pintype "input"))
    )
    (net (code "71") (name "Net-(IC3A-QC)") (class "Default")
      (node (ref "IC3") (pin "2") (pinfunction "QC_2") (pintype "tri_state"))
      (node (ref "IC8") (pin "3") (pinfunction "I3_3") (pintype "input"))
    )
    (net (code "72") (name "Net-(IC3A-QD)") (class "Default")
      (node (ref "IC3") (pin "3") (pinfunction "QD_3") (pintype "tri_state"))
      (node (ref "IC8") (pin "4") (pinfunction "I4_4") (pintype "input"))
    )
    (net (code "73") (name "Net-(IC3A-QE)") (class "Default")
      (node (ref "IC3") (pin "4") (pinfunction "QE_4") (pintype "tri_state"))
      (node (ref "IC8") (pin "5") (pinfunction "I5_5") (pintype "input"))
    )
    (net (code "74") (name "Net-(IC3A-QF)") (class "Default")
      (node (ref "IC3") (pin "5") (pinfunction "QF_5") (pintype "tri_state"))
      (node (ref "IC8") (pin "6") (pinfunction "I6_6") (pintype "input"))
    )
    (net (code "75") (name "Net-(IC3A-QG)") (class "Default")
      (node (ref "IC3") (pin "6") (pinfunction "QG_6") (pintype "tri_state"))
      (node (ref "IC8") (pin "7") (pinfunction "I7_7") (pintype "input"))
    )
    (net (code "76") (name "Net-(IC3A-QH)") (class "Default")
      (node (ref "IC3") (pin "7") (pinfunction "QH_7") (pintype "tri_state"))
      (node (ref "IC8") (pin "8") (pinfunction "I8_8") (pintype "input"))
    )
    (net (code "77") (name "Net-(IC3A-QH*)") (class "Default")
      (node (ref "IC3") (pin "9") (pinfunction "QH*_9") (pintype "tri_state"))
      (node (ref "IC4") (pin "14") (pinfunction "SER_14") (pintype "input"))
    )
    (net (code "78") (name "Net-(IC4A-QA)") (class "Default")
      (node (ref "IC4") (pin "15") (pinfunction "QA_15") (pintype "tri_state"))
      (node (ref "IC9") (pin "1") (pinfunction "I1_1") (pintype "input"))
    )
    (net (code "79") (name "Net-(IC4A-QB)") (class "Default")
      (node (ref "IC4") (pin "1") (pinfunction "QB_1") (pintype "tri_state"))
      (node (ref "IC9") (pin "2") (pinfunction "I2_2") (pintype "input"))
    )
    (net (code "80") (name "Net-(IC4A-QC)") (class "Default")
      (node (ref "IC4") (pin "2") (pinfunction "QC_2") (pintype "tri_state"))
      (node (ref "IC9") (pin "3") (pinfunction "I3_3") (pintype "input"))
    )
    (net (code "81") (name "Net-(IC4A-QD)") (class "Default")
      (node (ref "IC4") (pin "3") (pinfunction "QD_3") (pintype "tri_state"))
      (node (ref "IC9") (pin "4") (pinfunction "I4_4") (pintype "input"))
    )
    (net (code "82") (name "Net-(IC4A-QE)") (class "Default")
      (node (ref "IC4") (pin "4") (pinfunction "QE_4") (pintype "tri_state"))
      (node (ref "IC9") (pin "5") (pinfunction "I5_5") (pintype "input"))
    )
    (net (code "83") (name "Net-(IC4A-QF)") (class "Default")
      (node (ref "IC4") (pin "5") (pinfunction "QF_5") (pintype "tri_state"))
      (node (ref "IC9") (pin "6") (pinfunction "I6_6") (pintype "input"))
    )
    (net (code "84") (name "Net-(IC4A-QG)") (class "Default")
      (node (ref "IC4") (pin "6") (pinfunction "QG_6") (pintype "tri_state"))
      (node (ref "IC9") (pin "7") (pinfunction "I7_7") (pintype "input"))
    )
    (net (code "85") (name "Net-(IC4A-QH)") (class "Default")
      (node (ref "IC4") (pin "7") (pinfunction "QH_7") (pintype "tri_state"))
      (node (ref "IC9") (pin "8") (pinfunction "I8_8") (pintype "input"))
    )
    (net (code "86") (name "Net-(IC4A-QH*)") (class "Default")
      (node (ref "IC4") (pin "9") (pinfunction "QH*_9") (pintype "tri_state"))
      (node (ref "IC5") (pin "14") (pinfunction "SER_14") (pintype "input"))
    )
    (net (code "87") (name "Net-(IC10-I1)") (class "Default")
      (node (ref "IC10") (pin "1") (pinfunction "I1_1") (pintype "input"))
      (node (ref "IC5") (pin "15") (pinfunction "QA_15") (pintype "tri_state"))
    )
    (net (code "88") (name "Net-(IC10-I2)") (class "Default")
      (node (ref "IC10") (pin "2") (pinfunction "I2_2") (pintype "input"))
      (node (ref "IC5") (pin "1") (pinfunction "QB_1") (pintype "tri_state"))
    )
    (net (code "89") (name "Net-(IC10-I3)") (class "Default")
      (node (ref "IC10") (pin "3") (pinfunction "I3_3") (pintype "input"))
      (node (ref "IC5") (pin "2") (pinfunction "QC_2") (pintype "tri_state"))
    )
    (net (code "90") (name "Net-(IC10-I4)") (class "Default")
      (node (ref "IC10") (pin "4") (pinfunction "I4_4") (pintype "input"))
      (node (ref "IC5") (pin "3") (pinfunction "QD_3") (pintype "tri_state"))
    )
    (net (code "91") (name "Net-(IC10-I5)") (class "Default")
      (node (ref "IC10") (pin "5") (pinfunction "I5_5") (pintype "input"))
      (node (ref "IC5") (pin "4") (pinfunction "QE_4") (pintype "tri_state"))
    )
    (net (code "92") (name "Net-(IC10-I6)") (class "Default")
      (node (ref "IC10") (pin "6") (pinfunction "I6_6") (pintype "input"))
      (node (ref "IC5") (pin "5") (pinfunction "QF_5") (pintype "tri_state"))
    )
    (net (code "93") (name "Net-(IC10-I7)") (class "Default")
      (node (ref "IC10") (pin "7") (pinfunction "I7_7") (pintype "input"))
      (node (ref "IC5") (pin "6") (pinfunction "QG_6") (pintype "tri_state"))
    )
    (net (code "94") (name "Net-(IC10-I8)") (class "Default")
      (node (ref "IC10") (pin "8") (pinfunction "I8_8") (pintype "input"))
      (node (ref "IC5") (pin "7") (pinfunction "QH_7") (pintype "tri_state"))
    )
    (net (code "95") (name "SEG1") (class "Default")
      (node (ref "D1") (pin "3") (pinfunction "CK1_3") (pintype "passive"))
    )
    (net (code "96") (name "SEG2") (class "Default")
      (node (ref "D2") (pin "3") (pinfunction "CK1_3") (pintype "passive"))
    )
    (net (code "97") (name "SEG3") (class "Default")
      (node (ref "D3") (pin "3") (pinfunction "CK1_3") (pintype "passive"))
    )
    (net (code "98") (name "SEG4") (class "Default")
      (node (ref "D4") (pin "3") (pinfunction "CK1_3") (pintype "passive"))
    )
    (net (code "99") (name "SEG5") (class "Default")
      (node (ref "D5") (pin "3") (pinfunction "CK1_3") (pintype "passive"))
    )
    (net (code "100") (name "SEG6") (class "Default")
      (node (ref "D6") (pin "3") (pinfunction "CK1_3") (pintype "passive"))
    )
    (net (code "101") (name "SEG7") (class "Default")
      (node (ref "D7") (pin "3") (pinfunction "CK1_3") (pintype "passive"))
    )
    (net (code "102") (name "SEG8") (class "Default")
      (node (ref "D8") (pin "3") (pinfunction "CK1_3") (pintype "passive"))
    )
    (net (code "103") (name "SEG9") (class "Default")
      (node (ref "D9") (pin "3") (pinfunction "CK1_3") (pintype "passive"))
    )
    (net (code "104") (name "SEG10") (class "Default")
      (node (ref "D10") (pin "3") (pinfunction "CK1_3") (pintype "passive"))
    )
    (net (code "105") (name "SEG11") (class "Default")
      (node (ref "D11") (pin "3") (pinfunction "CK1_3") (pintype "passive"))
    )
    (net (code "106") (name "SEG12") (class "Default")
      (node (ref "D12") (pin "3") (pinfunction "CK1_3") (pintype "passive"))
    )
    (net (code "107") (name "SEG13") (class "Default")
      (node (ref "D13") (pin "3") (pinfunction "CK1_3") (pintype "passive"))
    )
    (net (code "108") (name "SEG14") (class "Default")
      (node (ref "D14") (pin "3") (pinfunction "CK1_3") (pintype "passive"))
    )
    (net (code "109") (name "SEG15") (class "Default")
      (node (ref "D15") (pin "3") (pinfunction "CK1_3") (pintype "passive"))
    )
    (net (code "110") (name "SEG16") (class "Default")
      (node (ref "D16") (pin "3") (pinfunction "CK1_3") (pintype "passive"))
    )
    (net (code "112") (name "SEG18") (class "Default")
      (node (ref "D18") (pin "3") (pinfunction "CK1_3") (pintype "passive"))
    )
    (net (code "113") (name "SEG19") (class "Default")
      (node (ref "D19") (pin "3") (pinfunction "CK1_3") (pintype "passive"))
    )
    (net (code "114") (name "SEG20") (class "Default")
      (node (ref "D20") (pin "3") (pinfunction "CK1_3") (pintype "passive"))
    )
    (net (code "115") (name "SEG21") (class "Default")
      (node (ref "D21") (pin "3") (pinfunction "CK1_3") (pintype "passive"))
    )
    (net (code "116") (name "SEG22") (class "Default")
      (node (ref "D22") (pin "3") (pinfunction "CK1_3") (pintype "passive"))
    )
    (net (code "117") (name "SEG23") (class "Default")
      (node (ref "D23") (pin "3") (pinfunction "CK1_3") (pintype "passive"))
    )
    (net (code "118") (name "SEG24") (class "Default")
      (node (ref "D24") (pin "3") (pinfunction "CK1_3") (pintype "passive"))
    )
    (net (code "119") (name "SEG25") (class "Default")
      (node (ref "D25") (pin "3") (pinfunction "CK1_3") (pintype "passive"))
    )
    (net (code "120") (name "SEG26") (class "Default")
      (node (ref "D26") (pin "3") (pinfunction "CK1_3") (pintype "passive"))
    )
    (net (code "121") (name "SEG27") (class "Default")
      (node (ref "D27") (pin "3") (pinfunction "CK1_3") (pintype "passive"))
    )
    (net (code "122") (name "SEG28") (class "Default")
      (node (ref "D28") (pin "3") (pinfunction "CK1_3") (pintype "passive"))
    )
    (net (code "123") (name "SEG29") (class "Default")
      (node (ref "D29") (pin "3") (pinfunction "CK1_3") (pintype "passive"))
    )
    (net (code "124") (name "SEG30") (class "Default")
      (node (ref "D30") (pin "3") (pinfunction "CK1_3") (pintype "passive"))
    )
    (net (code "125") (name "SEG31") (class "Default")
      (node (ref "D31") (pin "3") (pinfunction "CK1_3") (pintype "passive"))
    )
    (net (code "126") (name "SEG32") (class "Default")
      (node (ref "D32") (pin "3") (pinfunction "CK1_3") (pintype "passive"))
    )
    (net (code "127") (name "SEG33") (class "Default")
      (node (ref "D33") (pin "3") (pinfunction "CK1_3") (pintype "passive"))
    )
    (net (code "128") (name "SEG34") (class "Default")
      (node (ref "D34") (pin "3") (pinfunction "CK1_3") (pintype "passive"))
    )
    (net (code "129") (name "SEG35") (class "Default")
      (node (ref "D35") (pin "3") (pinfunction "CK1_3") (pintype "passive"))
    )
    (net (code "130") (name "SEG36") (class "Default")
      (node (ref "D36") (pin "3") (pinfunction "CK1_3") (pintype "passive"))
    )
    (net (code "131") (name "SEG37") (class "Default")
      (node (ref "D37") (pin "3") (pinfunction "CK1_3") (pintype "passive"))
    )
    (net (code "132") (name "SEG38") (class "Default")
      (node (ref "D38") (pin "3") (pinfunction "CK1_3") (pintype "passive"))
    )
    (net (code "133") (name "SH_CP") (class "Default")
      (node (ref "IC1") (pin "11") (pinfunction "SCK_11") (pintype "input"))
      (node (ref "IC2") (pin "11") (pinfunction "SCK_11") (pintype "input"))
      (node (ref "IC3") (pin "11") (pinfunction "SCK_11") (pintype "input"))
      (node (ref "IC4") (pin "11") (pinfunction "SCK_11") (pintype "input"))
      (node (ref "IC5") (pin "11") (pinfunction "SCK_11") (pintype "input"))
    )
    (net (code "134") (name "ST_CP") (class "Default")
      (node (ref "IC1") (pin "12") (pinfunction "RCK_12") (pintype "input"))
      (node (ref "IC2") (pin "12") (pinfunction "RCK_12") (pintype "input"))
      (node (ref "IC3") (pin "12") (pinfunction "RCK_12") (pintype "input"))
      (node (ref "IC4") (pin "12") (pinfunction "RCK_12") (pintype "input"))
      (node (ref "IC5") (pin "12") (pinfunction "RCK_12") (pintype "input"))
    )
    (net (code "135") (name "VCC") (class "Default")
      (node (ref "IC10") (pin "10") (pinfunction "CD+_10") (pintype "passive"))
      (node (ref "IC6") (pin "10") (pinfunction "CD+_10") (pintype "passive"))
      (node (ref "IC7") (pin "10") (pinfunction "CD+_10") (pintype "passive"))
      (node (ref "IC8") (pin "10") (pinfunction "CD+_10") (pintype "passive"))
      (node (ref "IC9") (pin "10") (pinfunction "CD+_10") (pintype "passive"))
    )
    (net (code "136") (name "unconnected-(D1-CK2-Pad8)") (class "Default")
      (node (ref "D1") (pin "8") (pinfunction "CK2_8") (pintype "passive"))
    )
    (net (code "137") (name "unconnected-(D2-CK2-Pad8)") (class "Default")
      (node (ref "D2") (pin "8") (pinfunction "CK2_8") (pintype "passive"))
    )
    (net (code "138") (name "unconnected-(D3-CK2-Pad8)") (class "Default")
      (node (ref "D3") (pin "8") (pinfunction "CK2_8") (pintype "passive"))
    )
    (net (code "139") (name "unconnected-(D4-CK2-Pad8)") (class "Default")
      (node (ref "D4") (pin "8") (pinfunction "CK2_8") (pintype "passive"))
    )
    (net (code "140") (name "unconnected-(D5-CK2-Pad8)") (class "Default")
      (node (ref "D5") (pin "8") (pinfunction "CK2_8") (pintype "passive"))
    )
    (net (code "141") (name "unconnected-(D6-CK2-Pad8)") (class "Default")
      (node (ref "D6") (pin "8") (pinfunction "CK2_8") (pintype "passive"))
    )
    (net (code "142") (name "unconnected-(D7-CK2-Pad8)") (class "Default")
      (node (ref "D7") (pin "8") (pinfunction "CK2_8") (pintype "passive"))
    )
    (net (code "143") (name "unconnected-(D8-CK2-Pad8)") (class "Default")
      (node (ref "D8") (pin "8") (pinfunction "CK2_8") (pintype "passive"))
    )
    (net (code "144") (name "unconnected-(D9-CK2-Pad8)") (class "Default")
      (node (ref "D9") (pin "8") (pinfunction "CK2_8") (pintype "passive"))
    )
    (net (code "145") (name "unconnected-(D10-CK2-Pad8)") (class "Default")
      (node (ref "D10") (pin "8") (pinfunction "CK2_8") (pintype "passive"))
    )
    (net (code "146") (name "unconnected-(D11-CK2-Pad8)") (class "Default")
      (node (ref "D11") (pin "8") (pinfunction "CK2_8") (pintype "passive"))
    )
    (net (code "147") (name "unconnected-(D12-CK2-Pad8)") (class "Default")
      (node (ref "D12") (pin "8") (pinfunction "CK2_8") (pintype "passive"))
    )
    (net (code "148") (name "unconnected-(D13-CK2-Pad8)") (class "Default")
      (node (ref "D13") (pin "8") (pinfunction "CK2_8") (pintype "passive"))
    )
    (net (code "149") (name "unconnected-(D14-CK2-Pad8)") (class "Default")
      (node (ref "D14") (pin "8") (pinfunction "CK2_8") (pintype "passive"))
    )
    (net (code "150") (name "unconnected-(D15-CK2-Pad8)") (class "Default")
      (node (ref "D15") (pin "8") (pinfunction "CK2_8") (pintype "passive"))
    )
    (net (code "151") (name "unconnected-(D16-CK2-Pad8)") (class "Default")
      (node (ref "D16") (pin "8") (pinfunction "CK2_8") (pintype "passive"))
    )
    (net (code "152") (name "unconnected-(D17-CK1-Pad3)") (class "Default")
      (node (ref "D17") (pin "3") (pinfunction "CK1_3") (pintype "passive"))
    )
    (net (code "153") (name "unconnected-(D17-CK2-Pad8)") (class "Default")
      (node (ref "D17") (pin "8") (pinfunction "CK2_8") (pintype "passive"))
    )
    (net (code "154") (name "unconnected-(D18-CK2-Pad8)") (class "Default")
      (node (ref "D18") (pin "8") (pinfunction "CK2_8") (pintype "passive"))
    )
    (net (code "155") (name "unconnected-(D19-CK2-Pad8)") (class "Default")
      (node (ref "D19") (pin "8") (pinfunction "CK2_8") (pintype "passive"))
    )
    (net (code "156") (name "unconnected-(D20-CK2-Pad8)") (class "Default")
      (node (ref "D20") (pin "8") (pinfunction "CK2_8") (pintype "passive"))
    )
    (net (code "157") (name "unconnected-(D21-CK2-Pad8)") (class "Default")
      (node (ref "D21") (pin "8") (pinfunction "CK2_8") (pintype "passive"))
    )
    (net (code "158") (name "unconnected-(D22-CK2-Pad8)") (class "Default")
      (node (ref "D22") (pin "8") (pinfunction "CK2_8") (pintype "passive"))
    )
    (net (code "159") (name "unconnected-(D23-CK2-Pad8)") (class "Default")
      (node (ref "D23") (pin "8") (pinfunction "CK2_8") (pintype "passive"))
    )
    (net (code "160") (name "unconnected-(D24-CK2-Pad8)") (class "Default")
      (node (ref "D24") (pin "8") (pinfunction "CK2_8") (pintype "passive"))
    )
    (net (code "161") (name "unconnected-(D25-CK2-Pad8)") (class "Default")
      (node (ref "D25") (pin "8") (pinfunction "CK2_8") (pintype "passive"))
    )
    (net (code "162") (name "unconnected-(D26-CK2-Pad8)") (class "Default")
      (node (ref "D26") (pin "8") (pinfunction "CK2_8") (pintype "passive"))
    )
    (net (code "163") (name "unconnected-(D27-CK2-Pad8)") (class "Default")
      (node (ref "D27") (pin "8") (pinfunction "CK2_8") (pintype "passive"))
    )
    (net (code "164") (name "unconnected-(D28-CK2-Pad8)") (class "Default")
      (node (ref "D28") (pin "8") (pinfunction "CK2_8") (pintype "passive"))
    )
    (net (code "165") (name "unconnected-(D29-CK2-Pad8)") (class "Default")
      (node (ref "D29") (pin "8") (pinfunction "CK2_8") (pintype "passive"))
    )
    (net (code "166") (name "unconnected-(D30-CK2-Pad8)") (class "Default")
      (node (ref "D30") (pin "8") (pinfunction "CK2_8") (pintype "passive"))
    )
    (net (code "167") (name "unconnected-(D31-CK2-Pad8)") (class "Default")
      (node (ref "D31") (pin "8") (pinfunction "CK2_8") (pintype "passive"))
    )
    (net (code "168") (name "unconnected-(D32-CK2-Pad8)") (class "Default")
      (node (ref "D32") (pin "8") (pinfunction "CK2_8") (pintype "passive"))
    )
    (net (code "169") (name "unconnected-(D33-CK2-Pad8)") (class "Default")
      (node (ref "D33") (pin "8") (pinfunction "CK2_8") (pintype "passive"))
    )
    (net (code "170") (name "unconnected-(D34-CK2-Pad8)") (class "Default")
      (node (ref "D34") (pin "8") (pinfunction "CK2_8") (pintype "passive"))
    )
    (net (code "171") (name "unconnected-(D35-CK2-Pad8)") (class "Default")
      (node (ref "D35") (pin "8") (pinfunction "CK2_8") (pintype "passive"))
    )
    (net (code "172") (name "unconnected-(D36-CK2-Pad8)") (class "Default")
      (node (ref "D36") (pin "8") (pinfunction "CK2_8") (pintype "passive"))
    )
    (net (code "173") (name "unconnected-(D37-CK2-Pad8)") (class "Default")
      (node (ref "D37") (pin "8") (pinfunction "CK2_8") (pintype "passive"))
    )
    (net (code "174") (name "unconnected-(D38-CK2-Pad8)") (class "Default")
      (node (ref "D38") (pin "8") (pinfunction "CK2_8") (pintype "passive"))
    )
    (net (code "175") (name "unconnected-(IC5A-QH*-Pad9)") (class "Default")
      (node (ref "IC5") (pin "9") (pinfunction "QH*_9") (pintype "tri_state"))
    )
    (net (code "176") (name "unconnected-(IC6-O1-Pad18)") (class "Default")
      (node (ref "IC6") (pin "18") (pinfunction "O1_18") (pintype "open_collector"))
    )
    (net (code "177") (name "unconnected-(IC6-O2-Pad17)") (class "Default")
      (node (ref "IC6") (pin "17") (pinfunction "O2_17") (pintype "open_collector"))
    )
    (net (code "178") (name "unconnected-(IC6-O3-Pad16)") (class "Default")
      (node (ref "IC6") (pin "16") (pinfunction "O3_16") (pintype "open_collector"))
    )
    (net (code "179") (name "unconnected-(IC6-O4-Pad15)") (class "Default")
      (node (ref "IC6") (pin "15") (pinfunction "O4_15") (pintype "open_collector"))
    )
    (net (code "180") (name "unconnected-(IC6-O5-Pad14)") (class "Default")
      (node (ref "IC6") (pin "14") (pinfunction "O5_14") (pintype "open_collector"))
    )
    (net (code "181") (name "unconnected-(IC6-O6-Pad13)") (class "Default")
      (node (ref "IC6") (pin "13") (pinfunction "O6_13") (pintype "open_collector"))
    )
    (net (code "182") (name "unconnected-(IC6-O7-Pad12)") (class "Default")
      (node (ref "IC6") (pin "12") (pinfunction "O7_12") (pintype "open_collector"))
    )
    (net (code "183") (name "unconnected-(IC6-O8-Pad11)") (class "Default")
      (node (ref "IC6") (pin "11") (pinfunction "O8_11") (pintype "open_collector"))
    )
    (net (code "184") (name "unconnected-(IC7-O1-Pad18)") (class "Default")
      (node (ref "IC7") (pin "18") (pinfunction "O1_18") (pintype "open_collector"))
    )
    (net (code "185") (name "unconnected-(IC7-O2-Pad17)") (class "Default")
      (node (ref "IC7") (pin "17") (pinfunction "O2_17") (pintype "open_collector"))
    )
    (net (code "186") (name "unconnected-(IC7-O3-Pad16)") (class "Default")
      (node (ref "IC7") (pin "16") (pinfunction "O3_16") (pintype "open_collector"))
    )
    (net (code "187") (name "unconnected-(IC7-O4-Pad15)") (class "Default")
      (node (ref "IC7") (pin "15") (pinfunction "O4_15") (pintype "open_collector"))
    )
    (net (code "188") (name "unconnected-(IC7-O5-Pad14)") (class "Default")
      (node (ref "IC7") (pin "14") (pinfunction "O5_14") (pintype "open_collector"))
    )
    (net (code "189") (name "unconnected-(IC7-O6-Pad13)") (class "Default")
      (node (ref "IC7") (pin "13") (pinfunction "O6_13") (pintype "open_collector"))
    )
    (net (code "190") (name "unconnected-(IC7-O7-Pad12)") (class "Default")
      (node (ref "IC7") (pin "12") (pinfunction "O7_12") (pintype "open_collector"))
    )
    (net (code "191") (name "unconnected-(IC7-O8-Pad11)") (class "Default")
      (node (ref "IC7") (pin "11") (pinfunction "O8_11") (pintype "open_collector"))
    )
    (net (code "192") (name "unconnected-(IC8-O1-Pad18)") (class "Default")
      (node (ref "IC8") (pin "18") (pinfunction "O1_18") (pintype "open_collector"))
    )
    (net (code "193") (name "unconnected-(IC8-O2-Pad17)") (class "Default")
      (node (ref "IC8") (pin "17") (pinfunction "O2_17") (pintype "open_collector"))
    )
    (net (code "194") (name "unconnected-(IC8-O3-Pad16)") (class "Default")
      (node (ref "IC8") (pin "16") (pinfunction "O3_16") (pintype "open_collector"))
    )
    (net (code "195") (name "unconnected-(IC8-O4-Pad15)") (class "Default")
      (node (ref "IC8") (pin "15") (pinfunction "O4_15") (pintype "open_collector"))
    )
    (net (code "196") (name "unconnected-(IC8-O5-Pad14)") (class "Default")
      (node (ref "IC8") (pin "14") (pinfunction "O5_14") (pintype "open_collector"))
    )
    (net (code "197") (name "unconnected-(IC8-O6-Pad13)") (class "Default")
      (node (ref "IC8") (pin "13") (pinfunction "O6_13") (pintype "open_collector"))
    )
    (net (code "198") (name "unconnected-(IC8-O7-Pad12)") (class "Default")
      (node (ref "IC8") (pin "12") (pinfunction "O7_12") (pintype "open_collector"))
    )
    (net (code "199") (name "unconnected-(IC8-O8-Pad11)") (class "Default")
      (node (ref "IC8") (pin "11") (pinfunction "O8_11") (pintype "open_collector"))
    )
    (net (code "200") (name "unconnected-(IC9-O1-Pad18)") (class "Default")
      (node (ref "IC9") (pin "18") (pinfunction "O1_18") (pintype "open_collector"))
    )
    (net (code "201") (name "unconnected-(IC9-O2-Pad17)") (class "Default")
      (node (ref "IC9") (pin "17") (pinfunction "O2_17") (pintype "open_collector"))
    )
    (net (code "202") (name "unconnected-(IC9-O3-Pad16)") (class "Default")
      (node (ref "IC9") (pin "16") (pinfunction "O3_16") (pintype "open_collector"))
    )
    (net (code "203") (name "unconnected-(IC9-O4-Pad15)") (class "Default")
      (node (ref "IC9") (pin "15") (pinfunction "O4_15") (pintype "open_collector"))
    )
    (net (code "204") (name "unconnected-(IC9-O5-Pad14)") (class "Default")
      (node (ref "IC9") (pin "14") (pinfunction "O5_14") (pintype "open_collector"))
    )
    (net (code "205") (name "unconnected-(IC9-O6-Pad13)") (class "Default")
      (node (ref "IC9") (pin "13") (pinfunction "O6_13") (pintype "open_collector"))
    )
    (net (code "206") (name "unconnected-(IC9-O7-Pad12)") (class "Default")
      (node (ref "IC9") (pin "12") (pinfunction "O7_12") (pintype "open_collector"))
    )
    (net (code "207") (name "unconnected-(IC9-O8-Pad11)") (class "Default")
      (node (ref "IC9") (pin "11") (pinfunction "O8_11") (pintype "open_collector"))
    )
    (net (code "208") (name "unconnected-(IC10-O1-Pad18)") (class "Default")
      (node (ref "IC10") (pin "18") (pinfunction "O1_18") (pintype "open_collector"))
    )
    (net (code "209") (name "unconnected-(IC10-O2-Pad17)") (class "Default")
      (node (ref "IC10") (pin "17") (pinfunction "O2_17") (pintype "open_collector"))
    )
    (net (code "210") (name "unconnected-(IC10-O3-Pad16)") (class "Default")
      (node (ref "IC10") (pin "16") (pinfunction "O3_16") (pintype "open_collector"))
    )
    (net (code "211") (name "unconnected-(IC10-O4-Pad15)") (class "Default")
      (node (ref "IC10") (pin "15") (pinfunction "O4_15") (pintype "open_collector"))
    )
    (net (code "212") (name "unconnected-(IC10-O5-Pad14)") (class "Default")
      (node (ref "IC10") (pin "14") (pinfunction "O5_14") (pintype "open_collector"))
    )
    (net (code "213") (name "unconnected-(IC10-O6-Pad13)") (class "Default")
      (node (ref "IC10") (pin "13") (pinfunction "O6_13") (pintype "open_collector"))
    )
    (net (code "214") (name "unconnected-(IC10-O7-Pad12)") (class "Default")
      (node (ref "IC10") (pin "12") (pinfunction "O7_12") (pintype "open_collector"))
    )
    (net (code "215") (name "unconnected-(IC10-O8-Pad11)") (class "Default")
      (node (ref "IC10") (pin "11") (pinfunction "O8_11") (pintype "open_collector"))
    )
  )
)
